# Main.net
KiCad netlist of a schematic drawn in Altium Designer
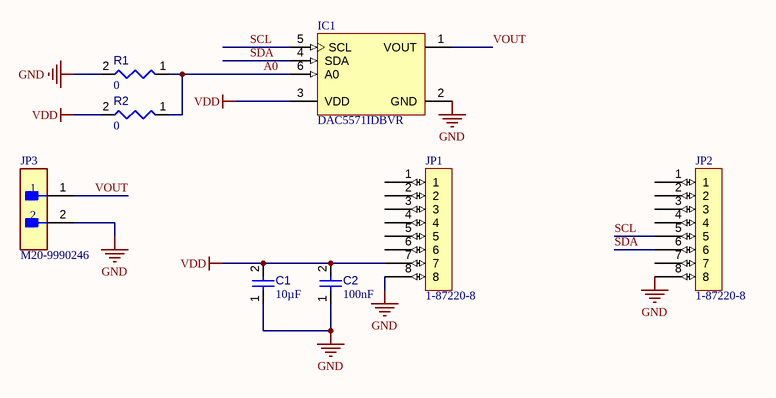
[diagram p0: Main.SchDoc]

(export (version "E")
  (design (tool "Eeschema 10.0.6"))
  (components
    (comp (ref "C1")
      (value "10µF")
      (footprint "CAPC0603(1608)100_L")
      (description "Chip Capacitor, 10µF +/-20%, 10V, 0603, Thickness 1 mm")
      (fields (field (name "TOLERANCE") "10%") (field (name "Comment") "Capacitor 10µF +/-20% 10V 0603"))
      (libsource (lib "Rice University") (part "CAP-NP-2"))
    )
    (comp (ref "C2")
      (value "100nF")
      (footprint "CAPC1608X90X40NL10T20")
      (description "Chip Capacitor, 100 nF, +/- 10%, 50 V, 0603 (1608 Metric)")
      (fields (field (name "TOLERANCE") "10%") (field (name "Comment") "Capacitor 100 nF +/-10% 50 V 0603"))
      (libsource (lib "Rice University") (part "CAP-NP-2"))
    )
    (comp (ref "IC1")
      (value "DAC5571IDBVR")
      (footprint "TI-DBV6_L")
      (description "8 Bit Digital to Analog Converter 1 SOT-23-6")
      (libsource (lib "Rice University") (part "TI-DACX571DBV6"))
    )
    (comp (ref "JP1")
      (value "1-87220-8")
      (footprint "1-87220-8-Footprint-1")
      (description "Conn Unshrouded Header HDR 1x8 POS 2.54mm Solder ST Thru-Hole Carton")
      (libsource (lib "Rice University") (part "1-87220-8-Symbol-1"))
    )
    (comp (ref "JP2")
      (value "1-87220-8")
      (footprint "1-87220-8-Footprint-1")
      (description "Conn Unshrouded Header HDR 1x8 POS 2.54mm Solder ST Thru-Hole Carton")
      (libsource (lib "Rice University") (part "1-87220-8-Symbol-1"))
    )
    (comp (ref "JP3")
      (value "M20-9990246")
      (footprint "FP-M20-9990246-MFG")
      (description "2.54mm (0.1\") Pitch SIL Vertical PC Tail Pin Header, 6.1mm mating pin height, tin, 2 contacts")
      (libsource (lib "Rice University") (part "3bc925449376181038e59eaffc5286c"))
    )
    (comp (ref "R1")
      (value "0")
      (footprint "RESC1608X55X25ML10T15")
      (description "Chip Resistor, 100 KOhm, +/- 1%, 0.1 W, -55 to 155 degC, 0603 (1608 Metric)")
      (fields (field (name "TOLERANCE") "1%") (field (name "POWER") "100mW"))
      (libsource (lib "Rice University") (part "RES-2"))
    )
    (comp (ref "R2")
      (value "0")
      (footprint "RESC1608X55X25ML10T15")
      (description "Chip Resistor, 100 KOhm, +/- 1%, 0.1 W, -55 to 155 degC, 0603 (1608 Metric)")
      (fields (field (name "TOLERANCE") "1%") (field (name "POWER") "100mW"))
      (libsource (lib "Rice University") (part "RES-2"))
    )
  )
  (nets
    (net (code "1") (name "/A0") (class "Default")
      (node (ref "IC1") (pin "6") (pinfunction "A0_6") (pintype "input"))
      (node (ref "R1") (pin "1") (pinfunction "1_1") (pintype "passive"))
      (node (ref "R2") (pin "1") (pinfunction "1_1") (pintype "passive"))
    )
    (net (code "2") (name "/SCL") (class "Default")
      (node (ref "IC1") (pin "5") (pinfunction "SCL_5") (pintype "input"))
      (node (ref "JP2") (pin "5") (pinfunction "5_5") (pintype "bidirectional"))
    )
    (net (code "3") (name "/SDA") (class "Default")
      (node (ref "IC1") (pin "4") (pinfunction "SDA_4") (pintype "input"))
      (node (ref "JP2") (pin "6") (pinfunction "6_6") (pintype "bidirectional"))
    )
    (net (code "4") (name "/VOUT") (class "Default")
      (node (ref "IC1") (pin "1") (pinfunction "VOUT_1") (pintype "tri_state"))
      (node (ref "JP3") (pin "1") (pinfunction "1_1") (pintype "passive"))
    )
    (net (code "5") (name "GND") (class "Default")
      (node (ref "C1") (pin "1") (pinfunction "1_1") (pintype "passive"))
      (node (ref "C2") (pin "1") (pinfunction "1_1") (pintype "passive"))
      (node (ref "IC1") (pin "2") (pinfunction "GND_2") (pintype "power_in"))
      (node (ref "JP1") (pin "8") (pinfunction "8_8") (pintype "bidirectional"))
      (node (ref "JP2") (pin "8") (pinfunction "8_8") (pintype "bidirectional"))
      (node (ref "JP3") (pin "2") (pinfunction "2_2") (pintype "passive"))
      (node (ref "R1") (pin "2") (pinfunction "2_2") (pintype "passive"))
    )
    (net (code "6") (name "VDD") (class "Default")
      (node (ref "C1") (pin "2") (pinfunction "2_2") (pintype "passive"))
      (node (ref "C2") (pin "2") (pinfunction "2_2") (pintype "passive"))
      (node (ref "IC1") (pin "3") (pinfunction "VDD_3") (pintype "power_in"))
      (node (ref "JP1") (pin "7") (pinfunction "7_7") (pintype "bidirectional"))
      (node (ref "R2") (pin "2") (pinfunction "2_2") (pintype "passive"))
    )
    (net (code "7") (name "unconnected-(JP1-Pad1)") (class "Default")
      (node (ref "JP1") (pin "1") (pinfunction "1_1") (pintype "bidirectional"))
    )
    (net (code "8") (name "unconnected-(JP1-Pad2)") (class "Default")
      (node (ref "JP1") (pin "2") (pinfunction "2_2") (pintype "bidirectional"))
    )
    (net (code "9") (name "unconnected-(JP1-Pad3)") (class "Default")
      (node (ref "JP1") (pin "3") (pinfunction "3_3") (pintype "bidirectional"))
    )
    (net (code "10") (name "unconnected-(JP1-Pad4)") (class "Default")
      (node (ref "JP1") (pin "4") (pinfunction "4_4") (pintype "bidirectional"))
    )
    (net (code "11") (name "unconnected-(JP1-Pad5)") (class "Default")
      (node (ref "JP1") (pin "5") (pinfunction "5_5") (pintype "bidirectional"))
    )
    (net (code "12") (name "unconnected-(JP1-Pad6)") (class "Default")
      (node (ref "JP1") (pin "6") (pinfunction "6_6") (pintype "bidirectional"))
    )
    (net (code "13") (name "unconnected-(JP2-Pad1)") (class "Default")
      (node (ref "JP2") (pin "1") (pinfunction "1_1") (pintype "bidirectional"))
    )
    (net (code "14") (name "unconnected-(JP2-Pad2)") (class "Default")
      (node (ref "JP2") (pin "2") (pinfunction "2_2") (pintype "bidirectional"))
    )
    (net (code "15") (name "unconnected-(JP2-Pad3)") (class "Default")
      (node (ref "JP2") (pin "3") (pinfunction "3_3") (pintype "bidirectional"))
    )
    (net (code "16") (name "unconnected-(JP2-Pad4)") (class "Default")
      (node (ref "JP2") (pin "4") (pinfunction "4_4") (pintype "bidirectional"))
    )
    (net (code "17") (name "unconnected-(JP2-Pad7)") (class "Default")
      (node (ref "JP2") (pin "7") (pinfunction "7_7") (pintype "bidirectional"))
    )
  )
)
